# 04_-_Display.net
KiCad netlist of a schematic drawn in Altium Designer
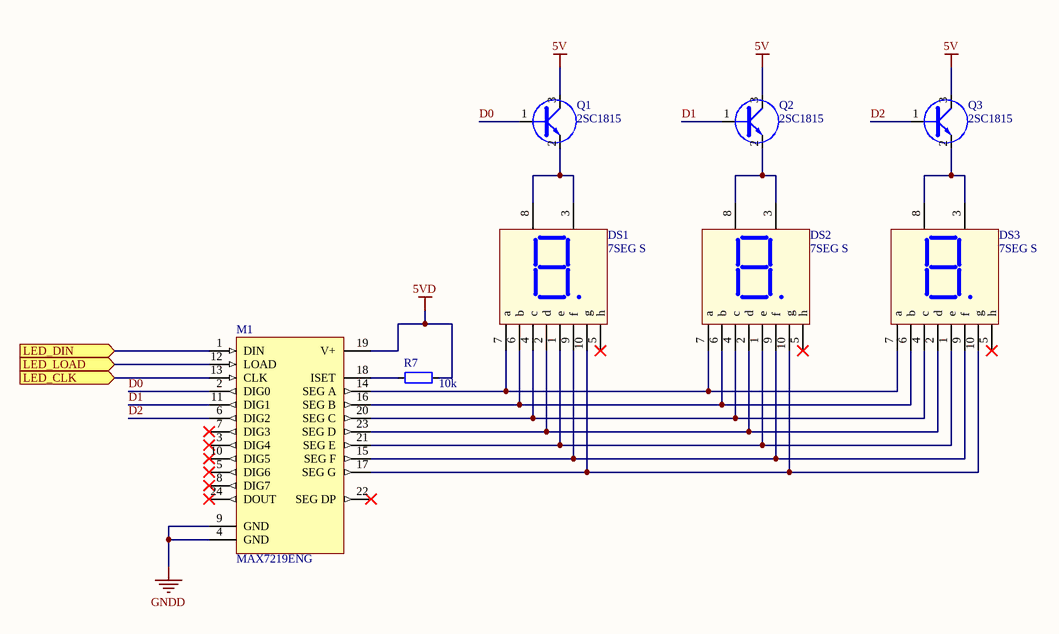
[diagram p0: [04] - Display.SchDoc]

(export (version "E")
  (design (tool "Eeschema 10.0.6"))
  (components
    (comp (ref "DS1")
      (value "7SEG S")
      (footprint "7SEGS")
      (description "Single 7 Seg Dipslay")
      (libsource (lib "My Library") (part "LED7S"))
    )
    (comp (ref "DS2")
      (value "7SEG S")
      (footprint "7SEGS")
      (description "Single 7 Seg Dipslay")
      (libsource (lib "My Library") (part "LED7S"))
    )
    (comp (ref "DS3")
      (value "7SEG S")
      (footprint "7SEGS")
      (description "Single 7 Seg Dipslay")
      (libsource (lib "My Library") (part "LED7S"))
    )
    (comp (ref "M1")
      (value "MAX7219ENG")
      (footprint "DIP24/W0.3")
      (description "Serially Interfaced, 8-Digit LED Display Driver")
      (fields (field (name "PUBLISHER") "Altium Limited"))
      (libsource (lib "My Library") (part "MAX7219ENG"))
    )
    (comp (ref "Q1")
      (value "2SC1815")
      (footprint "SOT23D")
      (description "NPN 600mW, ECB")
      (libsource (lib "My Library") (part "2SC1815"))
    )
    (comp (ref "Q2")
      (value "2SC1815")
      (footprint "SOT23D")
      (description "NPN 600mW, ECB")
      (libsource (lib "My Library") (part "2SC1815"))
    )
    (comp (ref "Q3")
      (value "2SC1815")
      (footprint "SOT23D")
      (description "NPN 600mW, ECB")
      (libsource (lib "My Library") (part "2SC1815"))
    )
    (comp (ref "R7")
      (value "10k")
      (footprint "RES-SMD-0805")
      (description "Resistor")
      (fields
        (field (name "MANUFACTURER") "Generic Components")
        (field (name "PUBLISHER") "Altium Hobart Technology Centre")
      )
      (libsource (lib "My Library") (part "Resistor - SMD"))
    )
  )
  (nets
    (net (code "1") (name "/D0") (class "Default")
      (node (ref "M1") (pin "2") (pinfunction "DIG0_2") (pintype "output"))
      (node (ref "Q1") (pin "1") (pinfunction "B_1") (pintype "passive"))
    )
    (net (code "2") (name "/D1") (class "Default")
      (node (ref "M1") (pin "11") (pinfunction "DIG1_11") (pintype "output"))
      (node (ref "Q2") (pin "1") (pinfunction "B_1") (pintype "passive"))
    )
    (net (code "3") (name "/D2") (class "Default")
      (node (ref "M1") (pin "6") (pinfunction "DIG2_6") (pintype "output"))
      (node (ref "Q3") (pin "1") (pinfunction "B_1") (pintype "passive"))
    )
    (net (code "4") (name "/LED_CLK") (class "Default")
      (node (ref "M1") (pin "13") (pinfunction "CLK_13") (pintype "input"))
    )
    (net (code "5") (name "/LED_DIN") (class "Default")
      (node (ref "M1") (pin "1") (pinfunction "DIN_1") (pintype "input"))
    )
    (net (code "6") (name "/LED_LOAD") (class "Default")
      (node (ref "M1") (pin "12") (pinfunction "LOAD_12") (pintype "input"))
    )
    (net (code "7") (name "5V") (class "Default")
      (node (ref "Q1") (pin "3") (pinfunction "C_3") (pintype "passive"))
      (node (ref "Q2") (pin "3") (pinfunction "C_3") (pintype "passive"))
      (node (ref "Q3") (pin "3") (pinfunction "C_3") (pintype "passive"))
    )
    (net (code "8") (name "5VD") (class "Default")
      (node (ref "M1") (pin "19") (pinfunction "V+_19") (pintype "power_in"))
      (node (ref "R7") (pin "1") (pinfunction "1_1") (pintype "passive"))
    )
    (net (code "9") (name "GNDD") (class "Default")
      (node (ref "M1") (pin "4") (pinfunction "GND_4") (pintype "power_in"))
      (node (ref "M1") (pin "9") (pinfunction "GND_9") (pintype "power_in"))
    )
    (net (code "10") (name "Net-(DS1-a)") (class "Default")
      (node (ref "DS1") (pin "7") (pinfunction "a_7") (pintype "passive"))
      (node (ref "DS2") (pin "7") (pinfunction "a_7") (pintype "passive"))
      (node (ref "DS3") (pin "7") (pinfunction "a_7") (pintype "passive"))
      (node (ref "M1") (pin "14") (pinfunction "SEG_A_14") (pintype "output"))
    )
    (net (code "11") (name "Net-(DS1-b)") (class "Default")
      (node (ref "DS1") (pin "6") (pinfunction "b_6") (pintype "passive"))
      (node (ref "DS2") (pin "6") (pinfunction "b_6") (pintype "passive"))
      (node (ref "DS3") (pin "6") (pinfunction "b_6") (pintype "passive"))
      (node (ref "M1") (pin "16") (pinfunction "SEG_B_16") (pintype "output"))
    )
    (net (code "12") (name "Net-(DS1-c)") (class "Default")
      (node (ref "DS1") (pin "4") (pinfunction "c_4") (pintype "passive"))
      (node (ref "DS2") (pin "4") (pinfunction "c_4") (pintype "passive"))
      (node (ref "DS3") (pin "4") (pinfunction "c_4") (pintype "passive"))
      (node (ref "M1") (pin "20") (pinfunction "SEG_C_20") (pintype "output"))
    )
    (net (code "13") (name "Net-(DS1-d)") (class "Default")
      (node (ref "DS1") (pin "2") (pinfunction "d_2") (pintype "passive"))
      (node (ref "DS2") (pin "2") (pinfunction "d_2") (pintype "passive"))
      (node (ref "DS3") (pin "2") (pinfunction "d_2") (pintype "passive"))
      (node (ref "M1") (pin "23") (pinfunction "SEG_D_23") (pintype "output"))
    )
    (net (code "14") (name "Net-(DS1-e)") (class "Default")
      (node (ref "DS1") (pin "1") (pinfunction "e_1") (pintype "passive"))
      (node (ref "DS2") (pin "1") (pinfunction "e_1") (pintype "passive"))
      (node (ref "DS3") (pin "1") (pinfunction "e_1") (pintype "passive"))
      (node (ref "M1") (pin "21") (pinfunction "SEG_E_21") (pintype "output"))
    )
    (net (code "15") (name "Net-(DS1-f)") (class "Default")
      (node (ref "DS1") (pin "9") (pinfunction "f_9") (pintype "passive"))
      (node (ref "DS2") (pin "9") (pinfunction "f_9") (pintype "passive"))
      (node (ref "DS3") (pin "9") (pinfunction "f_9") (pintype "passive"))
      (node (ref "M1") (pin "15") (pinfunction "SEG_F_15") (pintype "output"))
    )
    (net (code "16") (name "Net-(DS1-g)") (class "Default")
      (node (ref "DS1") (pin "10") (pinfunction "g_10") (pintype "passive"))
      (node (ref "DS2") (pin "10") (pinfunction "g_10") (pintype "passive"))
      (node (ref "DS3") (pin "10") (pinfunction "g_10") (pintype "passive"))
      (node (ref "M1") (pin "17") (pinfunction "SEG_G_17") (pintype "output"))
    )
    (net (code "17") (name "Net-(M1-ISET)") (class "Default")
      (node (ref "M1") (pin "18") (pinfunction "ISET_18") (pintype "passive"))
      (node (ref "R7") (pin "2") (pinfunction "2_2") (pintype "passive"))
    )
    (net (code "18") (name "Net-(Q1-E)") (class "Default")
      (node (ref "DS1") (pin "3") (pinfunction "Vcc_3") (pintype "passive"))
      (node (ref "DS1") (pin "8") (pinfunction "Vcc_8") (pintype "passive"))
      (node (ref "Q1") (pin "2") (pinfunction "E_2") (pintype "passive"))
    )
    (net (code "19") (name "Net-(Q2-E)") (class "Default")
      (node (ref "DS2") (pin "3") (pinfunction "Vcc_3") (pintype "passive"))
      (node (ref "DS2") (pin "8") (pinfunction "Vcc_8") (pintype "passive"))
      (node (ref "Q2") (pin "2") (pinfunction "E_2") (pintype "passive"))
    )
    (net (code "20") (name "Net-(Q3-E)") (class "Default")
      (node (ref "DS3") (pin "3") (pinfunction "Vcc_3") (pintype "passive"))
      (node (ref "DS3") (pin "8") (pinfunction "Vcc_8") (pintype "passive"))
      (node (ref "Q3") (pin "2") (pinfunction "E_2") (pintype "passive"))
    )
    (net (code "21") (name "unconnected-(DS1-h-Pad5)") (class "Default")
      (node (ref "DS1") (pin "5") (pinfunction "h_5") (pintype "passive+no_connect"))
    )
    (net (code "22") (name "unconnected-(DS2-h-Pad5)") (class "Default")
      (node (ref "DS2") (pin "5") (pinfunction "h_5") (pintype "passive+no_connect"))
    )
    (net (code "23") (name "unconnected-(DS3-h-Pad5)") (class "Default")
      (node (ref "DS3") (pin "5") (pinfunction "h_5") (pintype "passive+no_connect"))
    )
    (net (code "24") (name "unconnected-(M1-DIG3-Pad7)") (class "Default")
      (node (ref "M1") (pin "7") (pinfunction "DIG3_7") (pintype "output+no_connect"))
    )
    (net (code "25") (name "unconnected-(M1-DIG4-Pad3)") (class "Default")
      (node (ref "M1") (pin "3") (pinfunction "DIG4_3") (pintype "output+no_connect"))
    )
    (net (code "26") (name "unconnected-(M1-DIG5-Pad10)") (class "Default")
      (node (ref "M1") (pin "10") (pinfunction "DIG5_10") (pintype "output+no_connect"))
    )
    (net (code "27") (name "unconnected-(M1-DIG6-Pad5)") (class "Default")
      (node (ref "M1") (pin "5") (pinfunction "DIG6_5") (pintype "output+no_connect"))
    )
    (net (code "28") (name "unconnected-(M1-DIG7-Pad8)") (class "Default")
      (node (ref "M1") (pin "8") (pinfunction "DIG7_8") (pintype "output+no_connect"))
    )
    (net (code "29") (name "unconnected-(M1-DOUT-Pad24)") (class "Default")
      (node (ref "M1") (pin "24") (pinfunction "DOUT_24") (pintype "output+no_connect"))
    )
    (net (code "30") (name "unconnected-(M1-SEG_DP-Pad22)") (class "Default")
      (node (ref "M1") (pin "22") (pinfunction "SEG_DP_22") (pintype "output+no_connect"))
    )
  )
)
